# Power.net
KiCad netlist of a schematic drawn in Altium Designer
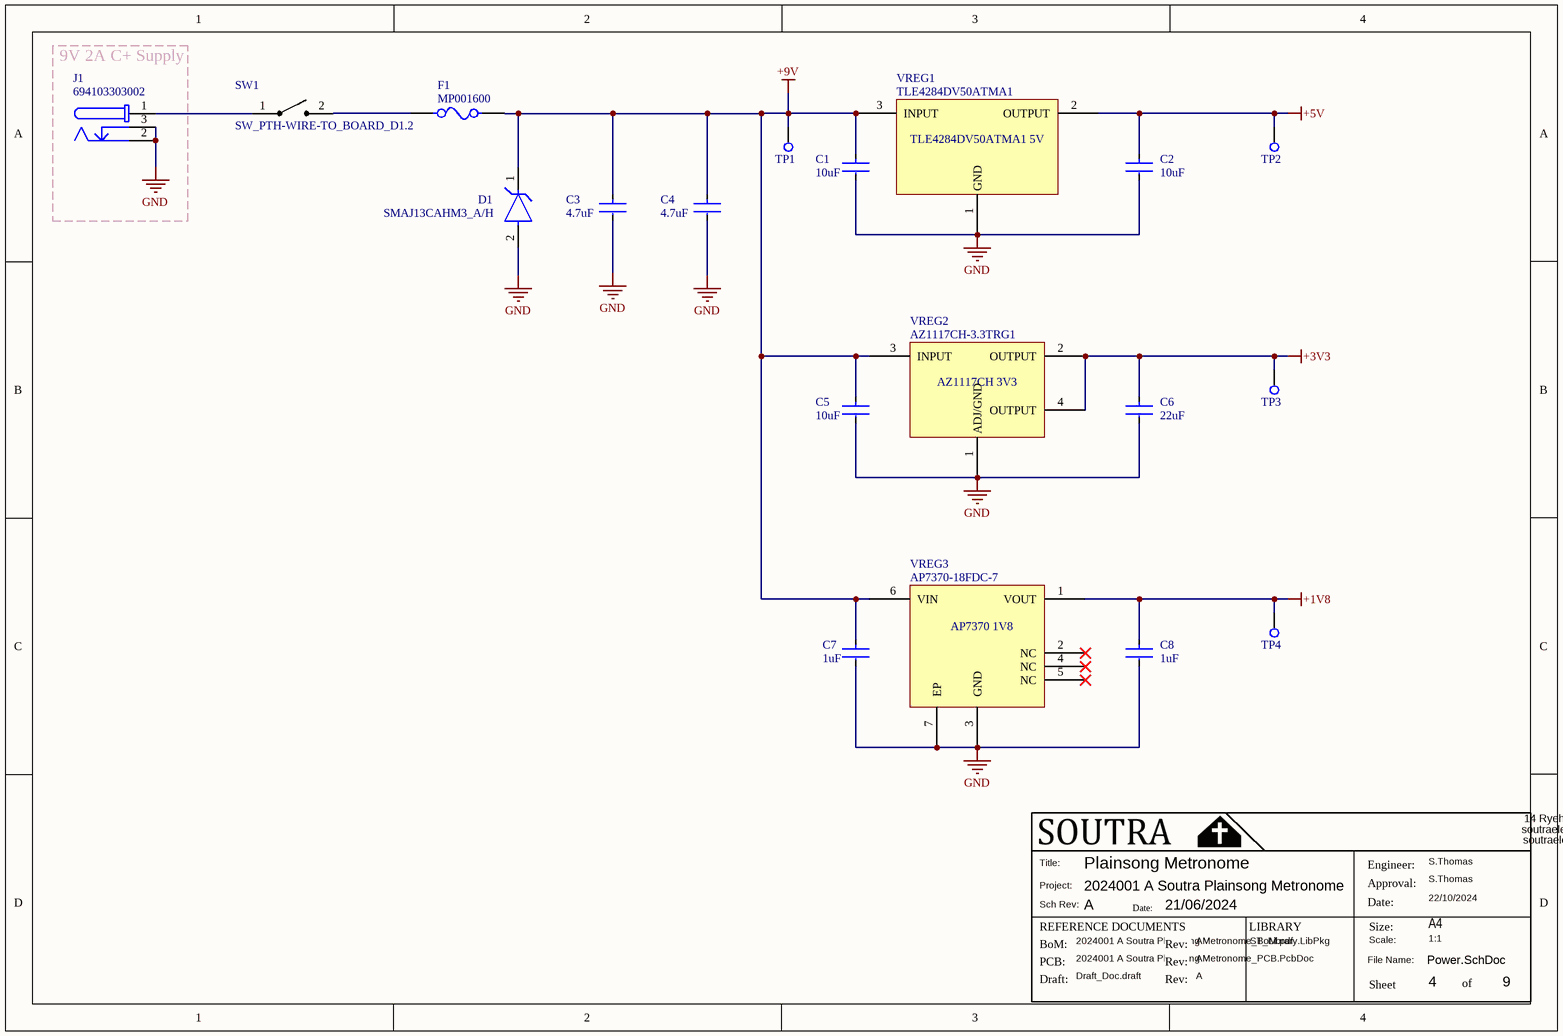
[diagram p0: Power.SchDoc]

(export (version "E")
  (design (tool "Eeschema 10.0.6"))
  (components
    (comp (ref "C1")
      (value "10uF")
      (footprint "CC1206-IPC_A")
      (description "Cap, 10Uf, 25V, Mlcc, 1206 Rohs Compliant: Yes")
      (fields
        (field (name "MANUFACTURER") "Walsin Technologies")
        (field (name "MANUFACTURER PART NUMBER") "1206B106K250CP")
      )
      (libsource (lib "ST_Library") (part "1206B106K250CP"))
    )
    (comp (ref "C2")
      (value "10uF")
      (footprint "CC1206-IPC_A")
      (description "Cap, 10Uf, 25V, Mlcc, 1206 Rohs Compliant: Yes")
      (fields
        (field (name "MANUFACTURER") "Walsin Technologies")
        (field (name "MANUFACTURER PART NUMBER") "1206B106K250CP")
      )
      (libsource (lib "ST_Library") (part "1206B106K250CP"))
    )
    (comp (ref "C3")
      (value "4.7uF")
      (footprint "CC1206-IPC_A")
      (fields
        (field (name "MANUFACTURER") "Samsung")
        (field (name "MANUFACTURER PART NUMBER") "CL31B475KAHNNNE")
      )
      (libsource (lib "ST_Library") (part "CL31B475KAHNNNE"))
    )
    (comp (ref "C4")
      (value "4.7uF")
      (footprint "CC1206-IPC_A")
      (fields
        (field (name "MANUFACTURER") "Samsung")
        (field (name "MANUFACTURER PART NUMBER") "CL31B475KAHNNNE")
      )
      (libsource (lib "ST_Library") (part "CL31B475KAHNNNE"))
    )
    (comp (ref "C5")
      (value "10uF")
      (footprint "CC1206-IPC_A")
      (description "Cap, 10Uf, 25V, Mlcc, 1206 Rohs Compliant: Yes")
      (fields
        (field (name "MANUFACTURER") "Walsin Technologies")
        (field (name "MANUFACTURER PART NUMBER") "1206B106K250CP")
      )
      (libsource (lib "ST_Library") (part "1206B106K250CP"))
    )
    (comp (ref "C6")
      (value "22uF")
      (footprint "CAPC2012X14L")
      (description "SMD Multilayer Ceramic Capacitor, 22 µF, 10 V, 0805 [2012 Metric], ± 20%, X5R, GRM Series")
      (fields
        (field (name "ALTERNATIVE SUPPLIER PART NUMBER") "490-10511-1-ND")
        (field (name "ALTERNATIVE PART") "C2012X5R1A226M125AB")
      )
      (libsource (lib "ST_Library") (part "GRM21BR61A226ME51L"))
    )
    (comp (ref "C7")
      (value "1uF")
      (footprint "CAPC1005X06L")
      (fields
        (field (name "MANUFACTURER") "Yageo")
        (field (name "MANUFACTURER PART NUMBER") "CC0402KRX5R6BB105")
        (field (name "ALTERNATIVE PART") "0402ZD105KAT2A")
      )
      (libsource (lib "ST_Library") (part "CC0402KRX5R6BB105"))
    )
    (comp (ref "C8")
      (value "1uF")
      (footprint "CAPC1005X06L")
      (fields
        (field (name "MANUFACTURER") "Yageo")
        (field (name "MANUFACTURER PART NUMBER") "CC0402KRX5R6BB105")
        (field (name "ALTERNATIVE PART") "0402ZD105KAT2A")
      )
      (libsource (lib "ST_Library") (part "CC0402KRX5R6BB105"))
    )
    (comp (ref "D1")
      (value "SMAJ13CAHM3_A/H")
      (footprint "SODFL511X229-2N")
      (description "TVS Diode, TRANSZORB SMAJ, Bidirectional, 13 V, 21.5 V, DO-214AC (SMA), 2 Pins")
      (fields (field (name "MANUFACTURER") "Vishay"))
      (libsource (lib "ST_Library") (part "SMAJ13CAHM3_A/H"))
    )
    (comp (ref "F1")
      (value "MP001600")
      (footprint "FUSE_3216X08L")
      (description "MULTICOMP PRO MP001600Fuse, Surface Mount, 1.5 A, Fast Acting, 72 VDC, 1206 [3216 Metric]")
      (fields (field (name "MANUFACTURER") "Multicomp"))
      (libsource (lib "ST_Library") (part "MP001600"))
    )
    (comp (ref "J1")
      (value "694103303002")
      (footprint "WURTH_694106301002")
      (description "Circular DC Power Connector")
      (fields (field (name "MANUFACTURER") "Wurth Electronics"))
      (libsource (lib "ST_Library") (part "694103303002"))
    )
    (comp (ref "SW1")
      (value "SW_PTH-WIRE-TO_BOARD_D1.2")
      (footprint "SW_PTH-Wire-to-Board-D1.2")
      (description "PTH Mounting Holes for Wire-to-board switch, 1.2mm diameter, >=17AWG")
      (libsource (lib "ST_Library") (part "SW_PTH-WIRE-TO_BOARD_D1.2"))
    )
    (comp (ref "TP1")
      (value "TP_CIRCLE_R1")
      (footprint "TP_CIRCLE_R1")
      (description "Test Point, SMD, Circular, Radius = 1mm")
      (libsource (lib "ST_Library") (part "TP_CIRCLE_R1"))
    )
    (comp (ref "TP2")
      (value "TP_CIRCLE_R1")
      (footprint "TP_CIRCLE_R1")
      (description "Test Point, SMD, Circular, Radius = 1mm")
      (libsource (lib "ST_Library") (part "TP_CIRCLE_R1"))
    )
    (comp (ref "TP3")
      (value "TP_CIRCLE_R1")
      (footprint "TP_CIRCLE_R1")
      (description "Test Point, SMD, Circular, Radius = 1mm")
      (libsource (lib "ST_Library") (part "TP_CIRCLE_R1"))
    )
    (comp (ref "TP4")
      (value "TP_CIRCLE_R1")
      (footprint "TP_CIRCLE_R1")
      (description "Test Point, SMD, Circular, Radius = 1mm")
      (libsource (lib "ST_Library") (part "TP_CIRCLE_R1"))
    )
    (comp (ref "VREG1")
      (value "TLE4284DV50ATMA1")
      (footprint "TO252-3-11_L")
      (fields (field (name "MANUFACTURER") "Infineon"))
      (libsource (lib "ST_Library") (part "TLE4284DV50ATMA1"))
    )
    (comp (ref "VREG2")
      (value "AZ1117CH-3.3TRG1")
      (footprint "SOT230P700X180-4L")
      (description "Fixed Positive LDO Regulator, 3.3V, 1.3V Dropout, BIPolar, PDSO3")
      (fields (field (name "MANUFACTURER") "Diodes"))
      (libsource (lib "ST_Library") (part "AZ1117CH-3.3TRG1"))
    )
    (comp (ref "VREG3")
      (value "AP7370-18FDC-7")
      (footprint "U-DFN2020EP65P201X201X63_HS-7L")
      (description "Fixed Positive LDO Regulator")
      (fields (field (name "MANUFACTURER") "Diodes"))
      (libsource (lib "ST_Library") (part "AP7370-18FDC-7"))
    )
  )
  (nets
    (net (code "1") (name "+1V8") (class "Default")
      (node (ref "C8") (pin "1") (pinfunction "1_1") (pintype "passive"))
      (node (ref "TP4") (pin "1") (pinfunction "1_1") (pintype "passive"))
      (node (ref "VREG3") (pin "1") (pinfunction "VOUT_1") (pintype "passive"))
    )
    (net (code "2") (name "+3V3") (class "Default")
      (node (ref "C6") (pin "1") (pinfunction "1_1") (pintype "passive"))
      (node (ref "TP3") (pin "1") (pinfunction "1_1") (pintype "passive"))
      (node (ref "VREG2") (pin "2") (pinfunction "OUTPUT_2") (pintype "passive"))
      (node (ref "VREG2") (pin "4") (pinfunction "OUTPUT_4") (pintype "passive"))
    )
    (net (code "3") (name "+5V") (class "Default")
      (node (ref "C2") (pin "1") (pinfunction "1_1") (pintype "passive"))
      (node (ref "TP2") (pin "1") (pinfunction "1_1") (pintype "passive"))
      (node (ref "VREG1") (pin "2") (pinfunction "OUTPUT_2") (pintype "passive"))
    )
    (net (code "4") (name "+9V") (class "Default")
      (node (ref "C1") (pin "1") (pinfunction "1_1") (pintype "passive"))
      (node (ref "C3") (pin "1") (pinfunction "1_1") (pintype "passive"))
      (node (ref "C4") (pin "1") (pinfunction "1_1") (pintype "passive"))
      (node (ref "C5") (pin "1") (pinfunction "1_1") (pintype "passive"))
      (node (ref "C7") (pin "1") (pinfunction "1_1") (pintype "passive"))
      (node (ref "D1") (pin "1") (pinfunction "C_1") (pintype "passive"))
      (node (ref "F1") (pin "2") (pinfunction "2_2") (pintype "passive"))
      (node (ref "TP1") (pin "1") (pinfunction "1_1") (pintype "passive"))
      (node (ref "VREG1") (pin "3") (pinfunction "INPUT_3") (pintype "passive"))
      (node (ref "VREG2") (pin "3") (pinfunction "INPUT_3") (pintype "passive"))
      (node (ref "VREG3") (pin "6") (pinfunction "VIN_6") (pintype "passive"))
    )
    (net (code "5") (name "GND") (class "Default")
      (node (ref "C1") (pin "2") (pinfunction "2_2") (pintype "passive"))
      (node (ref "C2") (pin "2") (pinfunction "2_2") (pintype "passive"))
      (node (ref "C3") (pin "2") (pinfunction "2_2") (pintype "passive"))
      (node (ref "C4") (pin "2") (pinfunction "2_2") (pintype "passive"))
      (node (ref "C5") (pin "2") (pinfunction "2_2") (pintype "passive"))
      (node (ref "C6") (pin "2") (pinfunction "2_2") (pintype "passive"))
      (node (ref "C7") (pin "2") (pinfunction "2_2") (pintype "passive"))
      (node (ref "C8") (pin "2") (pinfunction "2_2") (pintype "passive"))
      (node (ref "D1") (pin "2") (pinfunction "A_2") (pintype "passive"))
      (node (ref "J1") (pin "2") (pinfunction "2_2") (pintype "passive"))
      (node (ref "J1") (pin "3") (pinfunction "3_3") (pintype "passive"))
      (node (ref "VREG1") (pin "1") (pinfunction "GND_1") (pintype "passive"))
      (node (ref "VREG2") (pin "1") (pinfunction "ADJ/GND_1") (pintype "passive"))
      (node (ref "VREG3") (pin "3") (pinfunction "GND_3") (pintype "passive"))
      (node (ref "VREG3") (pin "7") (pinfunction "EP_7") (pintype "passive"))
    )
    (net (code "6") (name "Net-(F1-Pad1)") (class "Default")
      (node (ref "F1") (pin "1") (pinfunction "1_1") (pintype "passive"))
      (node (ref "SW1") (pin "2") (pinfunction "2_2") (pintype "passive"))
    )
    (net (code "7") (name "Net-(J1-Pad1)") (class "Default")
      (node (ref "J1") (pin "1") (pinfunction "1_1") (pintype "passive"))
      (node (ref "SW1") (pin "1") (pinfunction "1_1") (pintype "passive"))
    )
    (net (code "8") (name "unconnected-(VREG3-NC-Pad2)") (class "Default")
      (node (ref "VREG3") (pin "2") (pinfunction "NC_2") (pintype "passive+no_connect"))
    )
    (net (code "9") (name "unconnected-(VREG3-NC-Pad4)") (class "Default")
      (node (ref "VREG3") (pin "4") (pinfunction "NC_4") (pintype "passive+no_connect"))
    )
    (net (code "10") (name "unconnected-(VREG3-NC-Pad5)") (class "Default")
      (node (ref "VREG3") (pin "5") (pinfunction "NC_5") (pintype "passive+no_connect"))
    )
  )
)
